# featherULP.net
KiCad netlist of a schematic drawn in Altium Designer
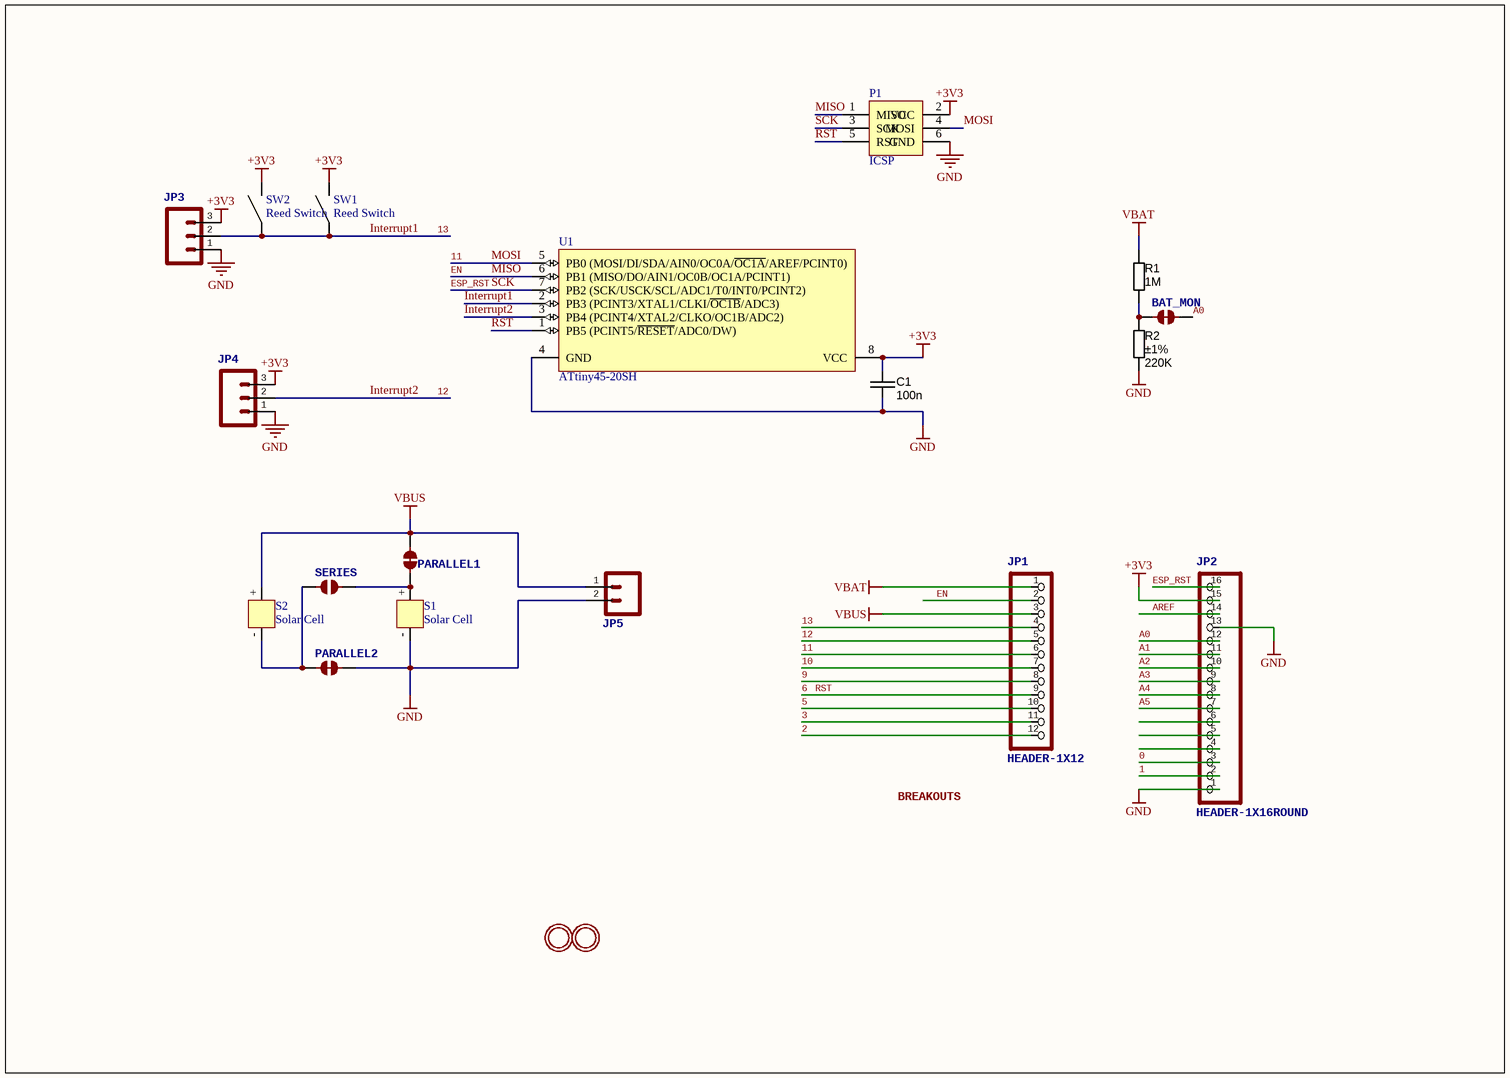
[diagram p0: featherULP.SchDoc]

(export (version "E")
  (design (tool "Eeschema 10.0.6"))
  (components
    (comp (ref "BAT_MON")
      (value "JUMPER-PAD-2-NC_BY_TRACENO_SILK")
      (footprint "PAD-JUMPER-2-NC_BY_TRACE_NO_SILK")
      (libsource (lib "SparkFun-Passives") (part "JUMPER-PAD-2-NC_BY_TRACENO_SILK"))
    )
    (comp (ref "C1")
      (value "100n")
      (footprint "CAPC1608X90N")
      (description "Capacitor SMD Cer 100nF 10% 50V X7R 0603")
      (fields (field (name "TOLERANCE") "±10%") (field (name "Comment") "approved sub OK"))
      (libsource (lib "PBL - Capacitors") (part "CAPC_100n_0603_X7R_50V_10%"))
    )
    (comp (ref "JP1")
      (value "HEADER-1X12")
      (footprint "1X12_ROUND")
      (fields (field (name "DRAWN") "KTOWN"))
      (libsource (lib "microbuilder") (part "HEADER-1X12"))
    )
    (comp (ref "JP2")
      (value "HEADER-1X16ROUND")
      (footprint "1X16_ROUND")
      (description "PIN HEADER")
      (fields (field (name "DRAWN") "KTOWN"))
      (libsource (lib "microbuilder") (part "HEADER-1X16ROUND"))
    )
    (comp (ref "JP3")
      (value "Header 3Standard 3-pin 0.1\" header. Use with straight break away headers (SKU : PRT-00116), right angle break away headers (PRT-00553), swiss pins (PRT-00743), machine pins (PRT-00117), and female headers (PRT-00115). Molex polarized connector foot print use with SKU : PRT-08232 with associated crimp pins and housings.")
      (footprint "1X03")
      (libsource (lib "SparkFun-Connectors") (part "M03PTH"))
    )
    (comp (ref "JP4")
      (value "Header 3Standard 3-pin 0.1\" header. Use with straight break away headers (SKU : PRT-00116), right angle break away headers (PRT-00553), swiss pins (PRT-00743), machine pins (PRT-00117), and female headers (PRT-00115). Molex polarized connector foot print use with SKU : PRT-08232 with associated crimp pins and housings.")
      (footprint "1X03")
      (libsource (lib "SparkFun-Connectors") (part "M03PTH"))
    )
    (comp (ref "JP5")
      (value "Standard 2-pin 0.1\" header. Use with  - straight break away headers ( PRT-00116) - right angle break away headers (PRT-00553) - swiss pins (PRT-00743) - machine pins (PRT-00117) - female headers (PRT-00115)   Molex polarized connector foot print use with: PRT-08233 with associated crimp pins and housings.  2.54_SCREWTERM for use with  PRT-10571.  3.5mm Screw Terminal footprints for  PRT-08084  5mm Screw Terminal footprints for use with PRT-08432")
      (footprint "1X02")
      (libsource (lib "SparkFun-Connectors") (part "M02PTH"))
    )
    (comp (ref "P1")
      (value "ICSP")
      (footprint "ICSP Pads - SMD")
      (description "Header, 3-Pin, Dual row")
      (fields (field (name "PUBLISHER") "Altium Limited"))
      (libsource (lib "Miscellaneous Connectors") (part "Header 3X2"))
    )
    (comp (ref "PARALLEL1")
      (value "JUMPER-PAD-2-NC_BY_TRACENO_SILK")
      (footprint "PAD-JUMPER-2-NC_BY_TRACE_NO_SILK")
      (libsource (lib "SparkFun-Passives") (part "JUMPER-PAD-2-NC_BY_TRACENO_SILK"))
    )
    (comp (ref "PARALLEL2")
      (value "JUMPER-PAD-2-NC_BY_TRACENO_SILK")
      (footprint "PAD-JUMPER-2-NC_BY_TRACE_NO_SILK")
      (libsource (lib "SparkFun-Passives") (part "JUMPER-PAD-2-NC_BY_TRACENO_SILK"))
    )
    (comp (ref "R1")
      (value "1M")
      (footprint "RESC2012X70N")
      (description "Resistor SMD chip 1M Ohm 0.125W 5% 0805")
      (fields (field (name "TOLERANCE") "±5%") (field (name "Comment") "Thick Film"))
      (libsource (lib "PBL - Resistors") (part "RES_1M_0805_5%"))
    )
    (comp (ref "R2")
      (value "220K")
      (footprint "RESC2012X70N")
      (description "Resistor SMD chip 205k Ohm 0.125W 1% 0805")
      (fields (field (name "TOLERANCE") "±1%") (field (name "Comment") "Thick Film"))
      (libsource (lib "PBL - Resistors") (part "RES_205K_0805_1%"))
    )
    (comp (ref "S1")
      (value "Solar Cell")
      (footprint "Solar Cell IXYS  KXOB22-01X8L-ND")
      (libsource (lib "Schlib1") (part "Solar Cell"))
    )
    (comp (ref "S2")
      (value "Solar Cell")
      (footprint "Solar Cell IXYS  KXOB22-01X8L-ND")
      (libsource (lib "Schlib1") (part "Solar Cell"))
    )
    (comp (ref "SERIES")
      (value "JUMPER-PAD-2-NO")
      (footprint "PAD-JUMPER-2-NO_NO_SILK")
      (libsource (lib "SparkFun-Passives") (part "JUMPER-PAD-2-NO"))
    )
    (comp (ref "SW1")
      (value "Reed Switch")
      (footprint "Reed Switch MDSM-4")
      (libsource (lib "Schlib1") (part "Reed Switch"))
    )
    (comp (ref "SW2")
      (value "Reed Switch")
      (footprint "Reed Switch MDSM-4")
      (libsource (lib "Schlib1") (part "Reed Switch"))
    )
    (comp (ref "U$31")
      (value "MOUNTINGHOLE2.5")
      (footprint "MOUNTINGHOLE_2.5_PLATED")
      (description "Mounting Hole   For #2 screws (0.086\"/2.18mm width, 0.094\"/2.4mm hole) use 2.5mm")
      (fields (field (name "DRAWN") "KTOWN"))
      (libsource (lib "microbuilder") (part "MOUNTINGHOLE2.5"))
    )
    (comp (ref "U$32")
      (value "MOUNTINGHOLE2.5")
      (footprint "MOUNTINGHOLE_2.5_PLATED")
      (description "Mounting Hole   For #2 screws (0.086\"/2.18mm width, 0.094\"/2.4mm hole) use 2.5mm")
      (fields (field (name "DRAWN") "KTOWN"))
      (libsource (lib "microbuilder") (part "MOUNTINGHOLE2.5"))
    )
    (comp (ref "U1")
      (value "ATtiny45-20SH")
      (footprint "8S2_N")
      (libsource (lib "Atmel Microcontroller tinyAVR") (part "ATtiny45-20SH"))
    )
  )
  (nets
    (net (code "1") (name "+3V3") (class "Default")
      (node (ref "C1") (pin "1") (pintype "passive"))
      (node (ref "JP2") (pin "15") (pinfunction "15_15") (pintype "passive"))
      (node (ref "JP3") (pin "3") (pinfunction "3_3") (pintype "passive"))
      (node (ref "JP4") (pin "3") (pinfunction "3_3") (pintype "passive"))
      (node (ref "P1") (pin "2") (pinfunction "VCC_2") (pintype "passive"))
      (node (ref "SW1") (pin "1") (pinfunction "1_1") (pintype "passive"))
      (node (ref "SW2") (pin "1") (pinfunction "1_1") (pintype "passive"))
      (node (ref "U1") (pin "8") (pinfunction "VCC_8") (pintype "power_in"))
    )
    (net (code "2") (name "/0") (class "Default")
      (node (ref "JP2") (pin "3") (pinfunction "3_3") (pintype "passive"))
    )
    (net (code "3") (name "/1") (class "Default")
      (node (ref "JP2") (pin "2") (pinfunction "2_2") (pintype "passive"))
    )
    (net (code "4") (name "/2") (class "Default")
      (node (ref "JP1") (pin "12") (pinfunction "12_12") (pintype "passive"))
    )
    (net (code "5") (name "/3") (class "Default")
      (node (ref "JP1") (pin "11") (pinfunction "11_11") (pintype "passive"))
    )
    (net (code "6") (name "/5") (class "Default")
      (node (ref "JP1") (pin "10") (pinfunction "10_10") (pintype "passive"))
    )
    (net (code "7") (name "/6") (class "Default")
      (node (ref "JP1") (pin "9") (pinfunction "9_9") (pintype "passive"))
      (node (ref "P1") (pin "5") (pinfunction "RST_5") (pintype "passive"))
      (node (ref "U1") (pin "1") (pinfunction "PB5_(PCINT5/~{RESET}/ADC0/DW)_1") (pintype "bidirectional"))
    )
    (net (code "8") (name "/9") (class "Default")
      (node (ref "JP1") (pin "8") (pinfunction "8_8") (pintype "passive"))
    )
    (net (code "9") (name "/10") (class "Default")
      (node (ref "JP1") (pin "7") (pinfunction "7_7") (pintype "passive"))
    )
    (net (code "10") (name "/11") (class "Default")
      (node (ref "JP1") (pin "6") (pinfunction "6_6") (pintype "passive"))
      (node (ref "P1") (pin "4") (pinfunction "MOSI_4") (pintype "passive"))
      (node (ref "U1") (pin "5") (pinfunction "PB0_(MOSI/DI/SDA/AIN0/OC0A/~{OC1A}/AREF/PCINT0)_5") (pintype "bidirectional"))
    )
    (net (code "11") (name "/12") (class "Default")
      (node (ref "JP1") (pin "5") (pinfunction "5_5") (pintype "passive"))
      (node (ref "JP4") (pin "2") (pinfunction "2_2") (pintype "passive"))
      (node (ref "U1") (pin "3") (pinfunction "PB4_(PCINT4/XTAL2/CLKO/OC1B/ADC2)_3") (pintype "bidirectional"))
    )
    (net (code "12") (name "/13") (class "Default")
      (node (ref "JP1") (pin "4") (pinfunction "4_4") (pintype "passive"))
      (node (ref "JP3") (pin "2") (pinfunction "2_2") (pintype "passive"))
      (node (ref "SW1") (pin "0") (pinfunction "0_0") (pintype "passive"))
      (node (ref "SW2") (pin "0") (pinfunction "0_0") (pintype "passive"))
      (node (ref "U1") (pin "2") (pinfunction "PB3_(PCINT3/XTAL1/CLKI/~{OC1B}/ADC3)_2") (pintype "bidirectional"))
    )
    (net (code "13") (name "/A0") (class "Default")
      (node (ref "BAT_MON") (pin "2") (pinfunction "2_2") (pintype "passive"))
      (node (ref "JP2") (pin "12") (pinfunction "12_12") (pintype "passive"))
    )
    (net (code "14") (name "/A1") (class "Default")
      (node (ref "JP2") (pin "11") (pinfunction "11_11") (pintype "passive"))
    )
    (net (code "15") (name "/A2") (class "Default")
      (node (ref "JP2") (pin "10") (pinfunction "10_10") (pintype "passive"))
    )
    (net (code "16") (name "/A3") (class "Default")
      (node (ref "JP2") (pin "9") (pinfunction "9_9") (pintype "passive"))
    )
    (net (code "17") (name "/A4") (class "Default")
      (node (ref "JP2") (pin "8") (pinfunction "8_8") (pintype "passive"))
    )
    (net (code "18") (name "/A5") (class "Default")
      (node (ref "JP2") (pin "7") (pinfunction "7_7") (pintype "passive"))
    )
    (net (code "19") (name "/AREF") (class "Default")
      (node (ref "JP2") (pin "14") (pinfunction "14_14") (pintype "passive"))
    )
    (net (code "20") (name "/EN") (class "Default")
      (node (ref "JP1") (pin "2") (pinfunction "2_2") (pintype "passive"))
      (node (ref "P1") (pin "1") (pinfunction "MISO_1") (pintype "passive"))
      (node (ref "U1") (pin "6") (pinfunction "PB1_(MISO/DO/AIN1/OC0B/OC1A/PCINT1)_6") (pintype "bidirectional"))
    )
    (net (code "21") (name "/ESP_RST") (class "Default")
      (node (ref "JP2") (pin "16") (pinfunction "16_16") (pintype "passive"))
      (node (ref "P1") (pin "3") (pinfunction "SCK_3") (pintype "passive"))
      (node (ref "U1") (pin "7") (pinfunction "PB2_(SCK/USCK/SCL/ADC1/T0/INT0/PCINT2)_7") (pintype "bidirectional"))
    )
    (net (code "22") (name "GND") (class "Default")
      (node (ref "C1") (pin "2") (pintype "passive"))
      (node (ref "JP2") (pin "1") (pinfunction "1_1") (pintype "passive"))
      (node (ref "JP2") (pin "13") (pinfunction "13_13") (pintype "passive"))
      (node (ref "JP3") (pin "1") (pinfunction "1_1") (pintype "passive"))
      (node (ref "JP4") (pin "1") (pinfunction "1_1") (pintype "passive"))
      (node (ref "JP5") (pin "2") (pinfunction "2_2") (pintype "passive"))
      (node (ref "P1") (pin "6") (pinfunction "GND_6") (pintype "passive"))
      (node (ref "PARALLEL2") (pin "2") (pinfunction "2_2") (pintype "passive"))
      (node (ref "R2") (pin "2") (pinfunction "2_2") (pintype "passive"))
      (node (ref "S1") (pin "-") (pinfunction "-_-") (pintype "passive"))
      (node (ref "U1") (pin "4") (pinfunction "GND_4") (pintype "power_in"))
    )
    (net (code "23") (name "Net-(BAT_MON-Pad1)") (class "Default")
      (node (ref "BAT_MON") (pin "1") (pinfunction "1_1") (pintype "passive"))
      (node (ref "R1") (pin "2") (pinfunction "2_2") (pintype "passive"))
      (node (ref "R2") (pin "1") (pinfunction "1_1") (pintype "passive"))
    )
    (net (code "24") (name "Net-(PARALLEL1-Pad1)") (class "Default")
      (node (ref "PARALLEL1") (pin "1") (pinfunction "1_1") (pintype "passive"))
      (node (ref "S1") (pin "+") (pinfunction "+_+") (pintype "passive"))
      (node (ref "SERIES") (pin "2") (pinfunction "2_2") (pintype "passive"))
    )
    (net (code "25") (name "Net-(PARALLEL2-Pad1)") (class "Default")
      (node (ref "PARALLEL2") (pin "1") (pinfunction "1_1") (pintype "passive"))
      (node (ref "S2") (pin "-") (pinfunction "-_-") (pintype "passive"))
      (node (ref "SERIES") (pin "1") (pinfunction "1_1") (pintype "passive"))
    )
    (net (code "26") (name "VBAT") (class "Default")
      (node (ref "JP1") (pin "1") (pinfunction "1_1") (pintype "passive"))
      (node (ref "R1") (pin "1") (pinfunction "1_1") (pintype "passive"))
    )
    (net (code "27") (name "VBUS") (class "Default")
      (node (ref "JP1") (pin "3") (pinfunction "3_3") (pintype "passive"))
      (node (ref "JP5") (pin "1") (pinfunction "1_1") (pintype "passive"))
      (node (ref "PARALLEL1") (pin "2") (pinfunction "2_2") (pintype "passive"))
      (node (ref "S2") (pin "+") (pinfunction "+_+") (pintype "passive"))
    )
    (net (code "28") (name "unconnected-(JP2-Pad4)") (class "Default")
      (node (ref "JP2") (pin "4") (pinfunction "4_4") (pintype "passive"))
    )
    (net (code "29") (name "unconnected-(JP2-Pad5)") (class "Default")
      (node (ref "JP2") (pin "5") (pinfunction "5_5") (pintype "passive"))
    )
    (net (code "30") (name "unconnected-(JP2-Pad6)") (class "Default")
      (node (ref "JP2") (pin "6") (pinfunction "6_6") (pintype "passive"))
    )
  )
)
